# V4-AddOnESP32-V002-cc1101.net
KiCad netlist of a schematic drawn in EAGLE
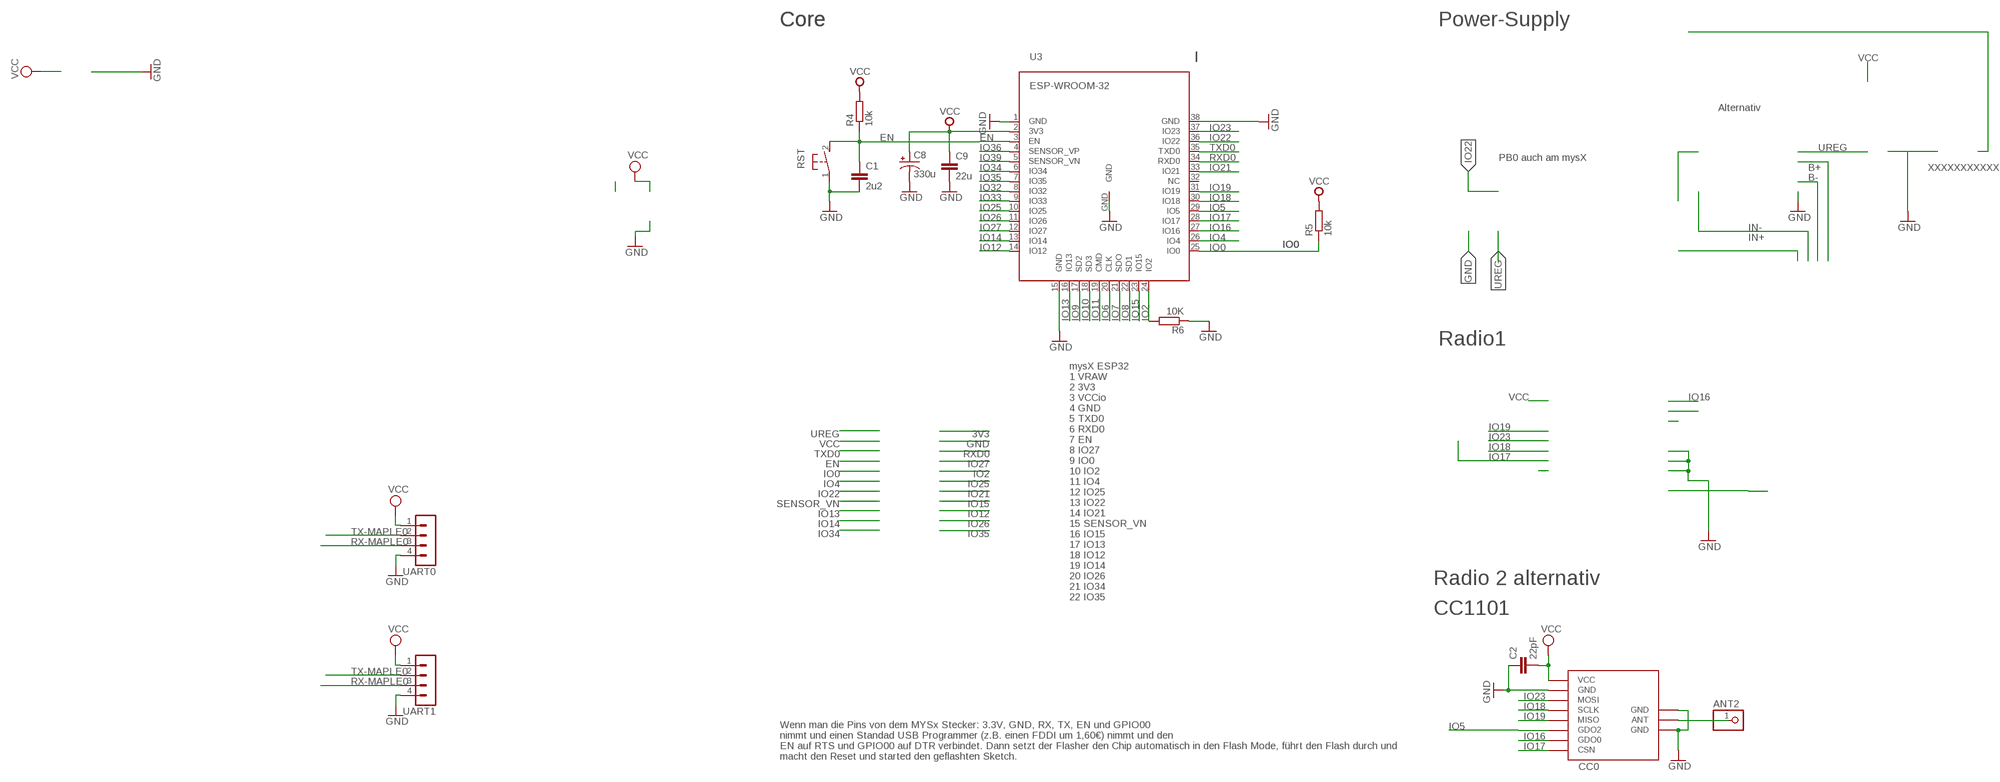
[diagram p0: schematic, sheet 1]

(export (version "E")
  (design (tool "Eeschema 10.0.6"))
  (components
    (comp (ref "ANT2")
      (value "PINHD-1X1")
      (footprint "eagle-import:1X01")
      (libsource (lib "eagle-import") (part "PINHD-1X1"))
    )
    (comp (ref "C1")
      (value "2u2")
      (footprint "eagle-import:C0805")
      (libsource (lib "eagle-import") (part "rcl@1_C-EUC0805"))
    )
    (comp (ref "C2")
      (value "22pF")
      (footprint "eagle-import:C0805")
      (libsource (lib "eagle-import") (part "C-EUC0805"))
    )
    (comp (ref "C8")
      (value "330u")
      (footprint "eagle-import:VISHAY_C")
      (libsource (lib "eagle-import") (part "CAP_POLSMD"))
    )
    (comp (ref "C9")
      (value "22u")
      (footprint "eagle-import:C0805")
      (libsource (lib "eagle-import") (part "rcl@1_C-EUC0805"))
    )
    (comp (ref "CC0")
      (value "CC1101")
      (footprint "eagle-import:CC1101_MODULE1_SMD")
      (libsource (lib "eagle-import") (part "CC1101_MODULE1SMD"))
    )
    (comp (ref "R4")
      (value "10k")
      (footprint "eagle-import:M0805")
      (libsource (lib "eagle-import") (part "rcl@1_R-EU_M0805"))
    )
    (comp (ref "R5")
      (value "10k")
      (footprint "eagle-import:R0603")
      (libsource (lib "eagle-import") (part "R-EU_R0603"))
    )
    (comp (ref "R6")
      (value "10K")
      (footprint "eagle-import:M0805")
      (libsource (lib "eagle-import") (part "R-EU_M0805"))
    )
    (comp (ref "RST")
      (value "DTSM-3")
      (footprint "eagle-import:DTSM-3")
      (libsource (lib "eagle-import") (part "DTSM-3"))
    )
    (comp (ref "U3")
      (value "ESP-WROOM-32")
      (footprint "eagle-import:ESP-WROOM-32")
      (libsource (lib "eagle-import") (part "ESP-WROOM-32"))
    )
    (comp (ref "UART0")
      (value "MA04-1")
      (footprint "eagle-import:MA04-1")
      (libsource (lib "eagle-import") (part "MA04-1"))
    )
    (comp (ref "UART1")
      (value "MA04-1")
      (footprint "eagle-import:MA04-1")
      (libsource (lib "eagle-import") (part "MA04-1"))
    )
  )
  (nets
    (net (code "4") (name "/EN") (class "Default")
      (node (ref "C1") (pin "1") (pinfunction "1_1") (pintype "passive"))
      (node (ref "R4") (pin "1") (pinfunction "1_1") (pintype "passive"))
      (node (ref "RST") (pin "2") (pinfunction "2_2") (pintype "passive"))
      (node (ref "U3") (pin "3") (pinfunction "EN_3") (pintype "bidirectional"))
    )
    (net (code "7") (name "/IO0") (class "Default")
      (node (ref "R5") (pin "1") (pinfunction "1_1") (pintype "passive"))
      (node (ref "U3") (pin "25") (pinfunction "IO0_25") (pintype "bidirectional"))
    )
    (net (code "8") (name "/IO2") (class "Default")
      (node (ref "R6") (pin "2") (pinfunction "2_2") (pintype "passive"))
      (node (ref "U3") (pin "24") (pinfunction "IO2_24") (pintype "bidirectional"))
    )
    (net (code "9") (name "/IO4") (class "Default")
      (node (ref "U3") (pin "26") (pinfunction "IO4_26") (pintype "bidirectional"))
    )
    (net (code "10") (name "/IO5") (class "Default")
      (node (ref "CC0") (pin "GDO2") (pinfunction "GDO2_GDO2") (pintype "bidirectional"))
      (node (ref "U3") (pin "29") (pinfunction "IO5_29") (pintype "bidirectional"))
    )
    (net (code "11") (name "/IO6") (class "Default")
      (node (ref "U3") (pin "20") (pinfunction "CLK_20") (pintype "bidirectional"))
    )
    (net (code "12") (name "/IO7") (class "Default")
      (node (ref "U3") (pin "21") (pinfunction "SDO_21") (pintype "bidirectional"))
    )
    (net (code "13") (name "/IO8") (class "Default")
      (node (ref "U3") (pin "22") (pinfunction "SD1_22") (pintype "bidirectional"))
    )
    (net (code "14") (name "/IO9") (class "Default")
      (node (ref "U3") (pin "17") (pinfunction "SD2_17") (pintype "bidirectional"))
    )
    (net (code "15") (name "/IO10") (class "Default")
      (node (ref "U3") (pin "18") (pinfunction "SD3_18") (pintype "bidirectional"))
    )
    (net (code "16") (name "/IO11") (class "Default")
      (node (ref "U3") (pin "19") (pinfunction "CMD_19") (pintype "bidirectional"))
    )
    (net (code "17") (name "/IO12") (class "Default")
      (node (ref "U3") (pin "14") (pinfunction "IO12_14") (pintype "bidirectional"))
    )
    (net (code "18") (name "/IO13") (class "Default")
      (node (ref "U3") (pin "16") (pinfunction "IO13_16") (pintype "bidirectional"))
    )
    (net (code "19") (name "/IO14") (class "Default")
      (node (ref "U3") (pin "13") (pinfunction "IO14_13") (pintype "bidirectional"))
    )
    (net (code "20") (name "/IO15") (class "Default")
      (node (ref "U3") (pin "23") (pinfunction "IO15_23") (pintype "bidirectional"))
    )
    (net (code "21") (name "/IO16") (class "Default")
      (node (ref "CC0") (pin "GDO0") (pinfunction "GDO0_GDO0") (pintype "bidirectional"))
      (node (ref "U3") (pin "27") (pinfunction "IO16_27") (pintype "bidirectional"))
    )
    (net (code "22") (name "/IO17") (class "Default")
      (node (ref "CC0") (pin "CSN") (pinfunction "CSN_CSN") (pintype "bidirectional"))
      (node (ref "U3") (pin "28") (pinfunction "IO17_28") (pintype "bidirectional"))
    )
    (net (code "23") (name "/IO18") (class "Default")
      (node (ref "CC0") (pin "SCLK") (pinfunction "SCLK_SCLK") (pintype "bidirectional"))
      (node (ref "U3") (pin "30") (pinfunction "IO18_30") (pintype "bidirectional"))
    )
    (net (code "24") (name "/IO19") (class "Default")
      (node (ref "CC0") (pin "MISO") (pinfunction "MISO_MISO") (pintype "bidirectional"))
      (node (ref "U3") (pin "31") (pinfunction "IO19_31") (pintype "bidirectional"))
    )
    (net (code "25") (name "/IO21") (class "Default")
      (node (ref "U3") (pin "33") (pinfunction "IO21_33") (pintype "bidirectional"))
    )
    (net (code "26") (name "/IO23") (class "Default")
      (node (ref "CC0") (pin "MOSI") (pinfunction "MOSI_MOSI") (pintype "bidirectional"))
      (node (ref "U3") (pin "37") (pinfunction "IO23_37") (pintype "bidirectional"))
    )
    (net (code "27") (name "/IO25") (class "Default")
      (node (ref "U3") (pin "10") (pinfunction "IO25_10") (pintype "bidirectional"))
    )
    (net (code "28") (name "/IO26") (class "Default")
      (node (ref "U3") (pin "11") (pinfunction "IO26_11") (pintype "bidirectional"))
    )
    (net (code "29") (name "/IO27") (class "Default")
      (node (ref "U3") (pin "12") (pinfunction "IO27_12") (pintype "bidirectional"))
    )
    (net (code "30") (name "/IO32") (class "Default")
      (node (ref "U3") (pin "8") (pinfunction "IO32_8") (pintype "bidirectional"))
    )
    (net (code "31") (name "/IO33") (class "Default")
      (node (ref "U3") (pin "9") (pinfunction "IO33_9") (pintype "bidirectional"))
    )
    (net (code "32") (name "/IO34") (class "Default")
      (node (ref "U3") (pin "6") (pinfunction "IO34_6") (pintype "bidirectional"))
    )
    (net (code "33") (name "/IO35") (class "Default")
      (node (ref "U3") (pin "7") (pinfunction "IO35_7") (pintype "bidirectional"))
    )
    (net (code "34") (name "/IO36") (class "Default")
      (node (ref "U3") (pin "4") (pinfunction "SENSOR_VP_4") (pintype "bidirectional"))
    )
    (net (code "35") (name "/IO39") (class "Default")
      (node (ref "U3") (pin "5") (pinfunction "SENSOR_VN_5") (pintype "bidirectional"))
    )
    (net (code "36") (name "/RX-MAPLE0") (class "Default")
      (node (ref "UART0") (pin "3") (pinfunction "3_3") (pintype "passive"))
      (node (ref "UART1") (pin "3") (pinfunction "3_3") (pintype "passive"))
    )
    (net (code "37") (name "/RXD0") (class "Default")
      (node (ref "U3") (pin "34") (pinfunction "RXD0_34") (pintype "bidirectional"))
    )
    (net (code "39") (name "/TX-MAPLE0") (class "Default")
      (node (ref "UART0") (pin "2") (pinfunction "2_2") (pintype "passive"))
      (node (ref "UART1") (pin "2") (pinfunction "2_2") (pintype "passive"))
    )
    (net (code "40") (name "/TXD0") (class "Default")
      (node (ref "U3") (pin "35") (pinfunction "TXD0_35") (pintype "bidirectional"))
    )
    (net (code "41") (name "GND") (class "Default")
      (node (ref "C1") (pin "2") (pinfunction "2_2") (pintype "passive"))
      (node (ref "C2") (pin "1") (pinfunction "1_1") (pintype "passive"))
      (node (ref "C8") (pin "-") (pinfunction "-_-") (pintype "passive"))
      (node (ref "C9") (pin "2") (pinfunction "2_2") (pintype "passive"))
      (node (ref "CC0") (pin "GND@0") (pinfunction "GND_GND@0") (pintype "power_in"))
      (node (ref "CC0") (pin "GND@1") (pinfunction "GND_GND@1") (pintype "power_in"))
      (node (ref "CC0") (pin "GND@2") (pinfunction "GND_GND@2") (pintype "power_in"))
      (node (ref "R6") (pin "1") (pinfunction "1_1") (pintype "passive"))
      (node (ref "RST") (pin "1") (pinfunction "1_1") (pintype "passive"))
      (node (ref "U3") (pin "1") (pinfunction "GND_1") (pintype "bidirectional"))
      (node (ref "U3") (pin "15") (pinfunction "GND_15") (pintype "bidirectional"))
      (node (ref "U3") (pin "38") (pinfunction "GND_38") (pintype "bidirectional"))
      (node (ref "U3") (pin "GND") (pinfunction "GND_GND") (pintype "bidirectional"))
      (node (ref "UART0") (pin "4") (pinfunction "4_4") (pintype "passive"))
      (node (ref "UART1") (pin "4") (pinfunction "4_4") (pintype "passive"))
    )
    (net (code "42") (name "IO22") (class "Default")
      (node (ref "U3") (pin "36") (pinfunction "IO22_36") (pintype "bidirectional"))
    )
    (net (code "43") (name "Net-(ANT2-Pad1)") (class "Default")
      (node (ref "ANT2") (pin "1") (pinfunction "1_1") (pintype "passive"))
      (node (ref "CC0") (pin "ANT") (pinfunction "ANT_ANT") (pintype "output"))
    )
    (net (code "45") (name "VCC") (class "Default")
      (node (ref "C2") (pin "2") (pinfunction "2_2") (pintype "passive"))
      (node (ref "C8") (pin "+") (pinfunction "+_+") (pintype "passive"))
      (node (ref "C9") (pin "1") (pinfunction "1_1") (pintype "passive"))
      (node (ref "CC0") (pin "VCC") (pinfunction "VCC_VCC") (pintype "power_in"))
      (node (ref "R4") (pin "2") (pinfunction "2_2") (pintype "passive"))
      (node (ref "R5") (pin "2") (pinfunction "2_2") (pintype "passive"))
      (node (ref "U3") (pin "2") (pinfunction "3V3_2") (pintype "bidirectional"))
      (node (ref "UART0") (pin "1") (pinfunction "1_1") (pintype "passive"))
      (node (ref "UART1") (pin "1") (pinfunction "1_1") (pintype "passive"))
    )
    (net (code "46") (name "unconnected-(U3-NC-Pad32)") (class "Default")
      (node (ref "U3") (pin "32") (pinfunction "NC_32") (pintype "bidirectional"))
    )
  )
)
